# OmniBotRemote.net
KiCad netlist of a schematic drawn in Altium Designer
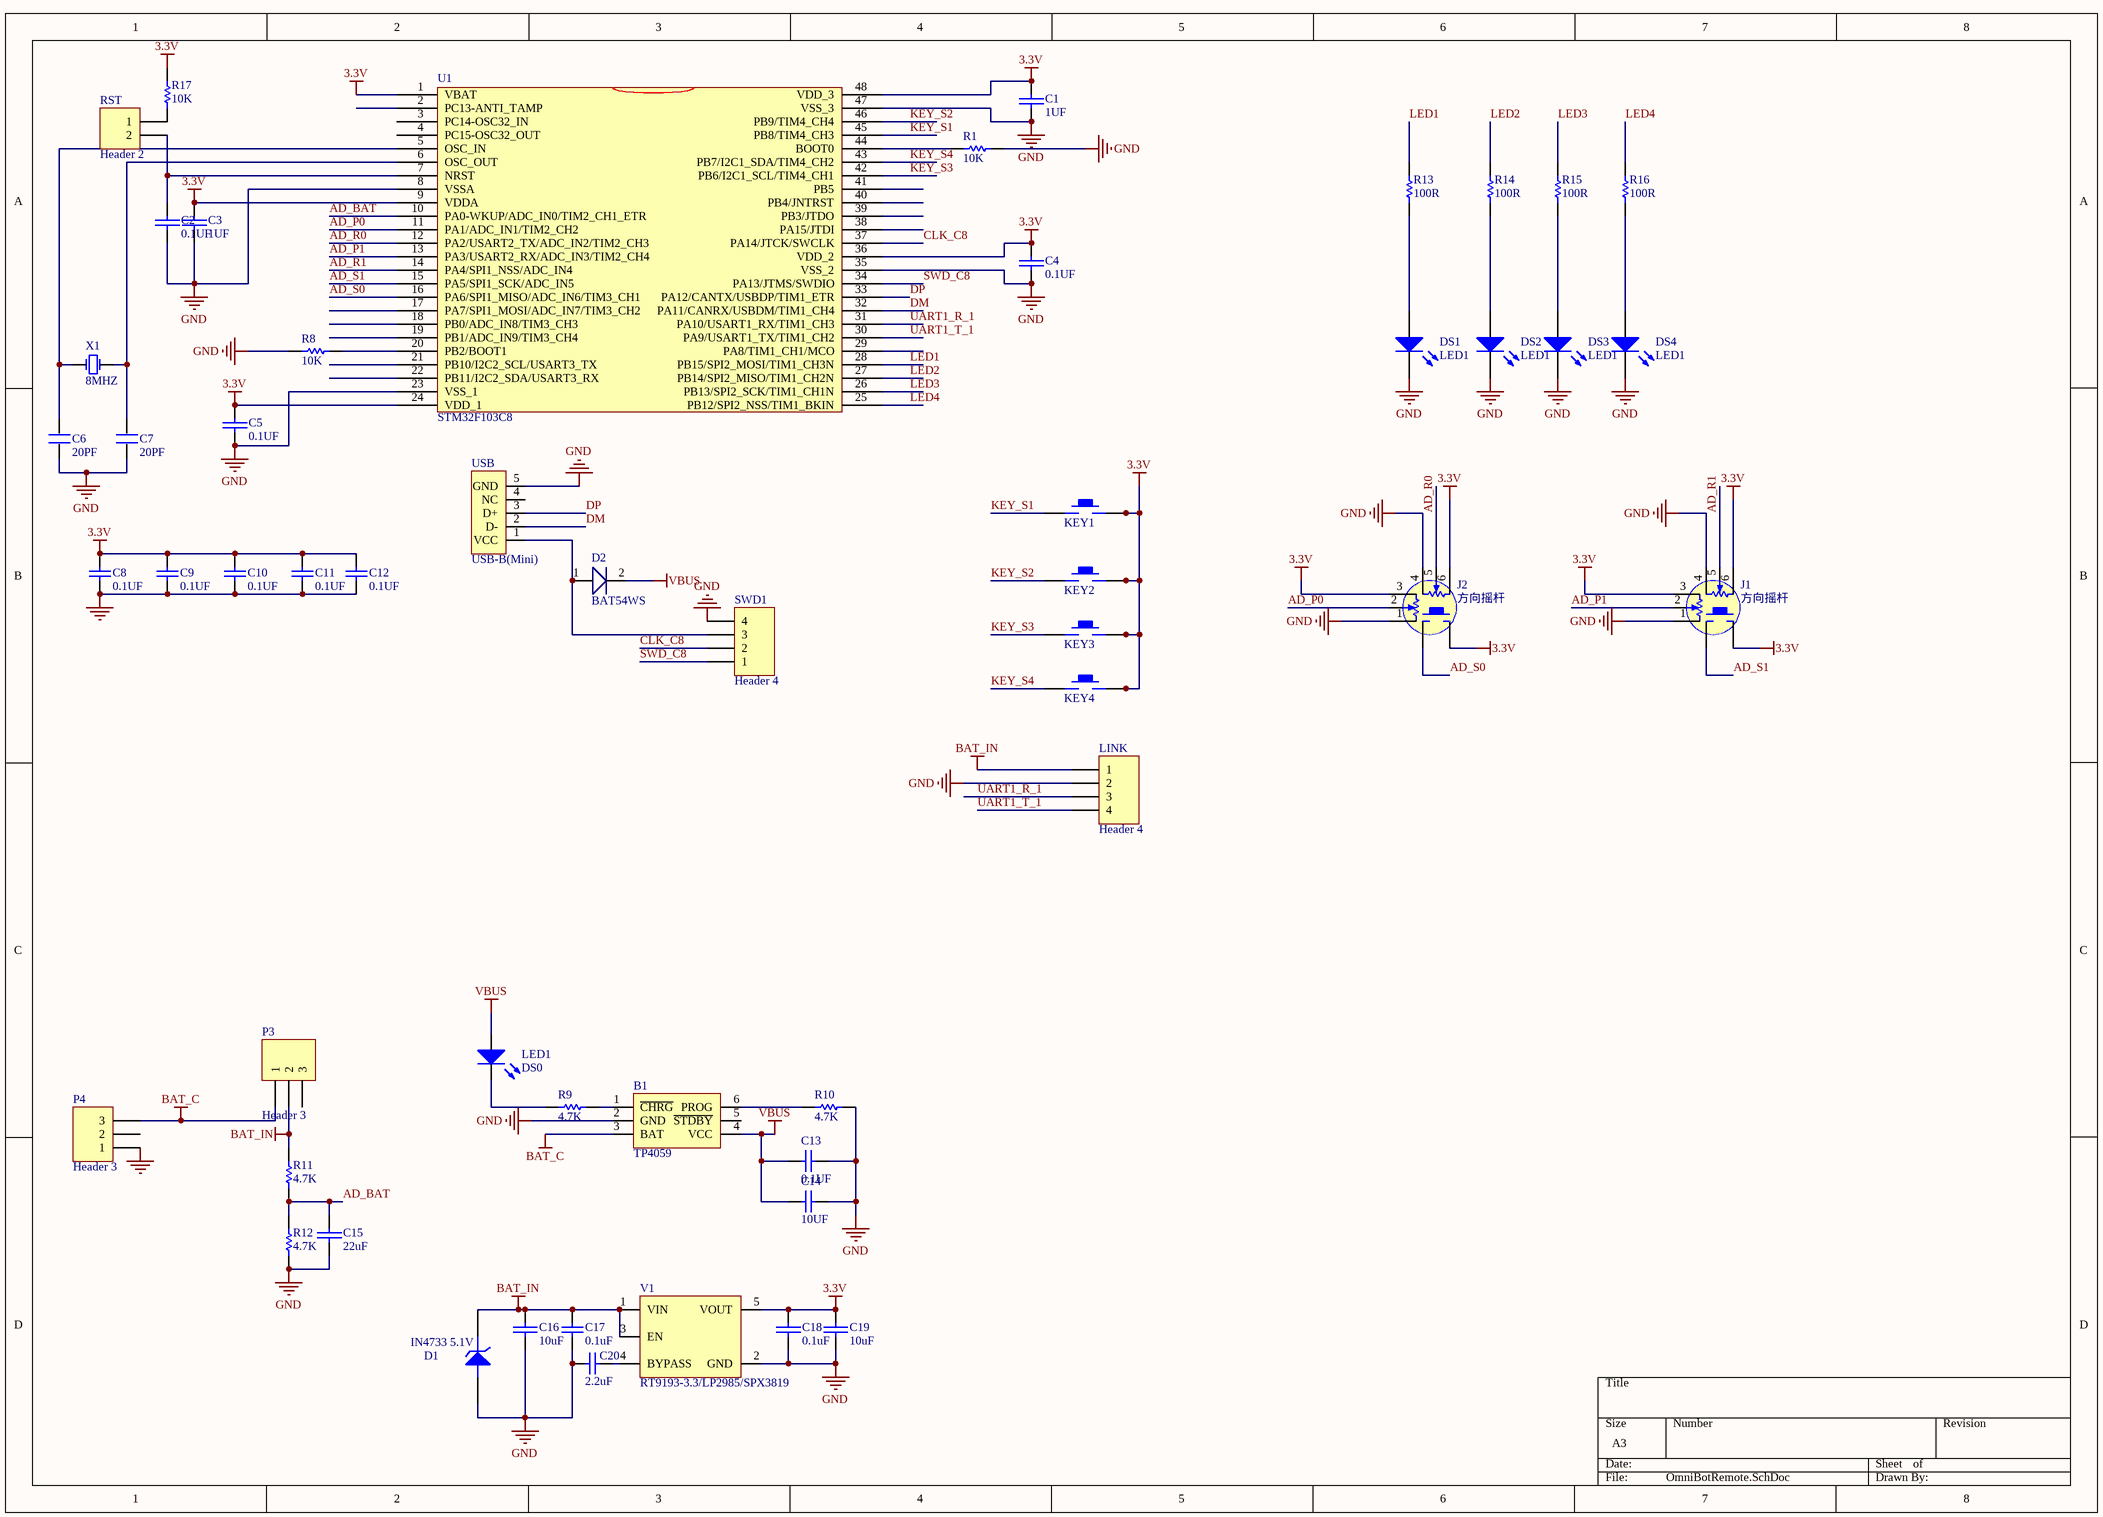
[diagram p0: OmniBotRemote.SchDoc]

(export (version "E")
  (design (tool "Eeschema 10.0.6"))
  (components
    (comp (ref "B1") (value "TP4059") (footprint "SOT23-6S") (libsource (lib "MiniFly ") (part "TP4059")))
    (comp (ref "C1")
      (value "1UF")
      (footprint "C 0402")
      (description "Capacitor")
      (libsource (lib "*") (part "CAP"))
    )
    (comp (ref "C2")
      (value "0.1UF")
      (footprint "C 0402")
      (description "Capacitor")
      (libsource (lib "*") (part "CAP"))
    )
    (comp (ref "C3")
      (value "1UF")
      (footprint "C 0402")
      (description "Capacitor")
      (libsource (lib "*") (part "CAP"))
    )
    (comp (ref "C4")
      (value "0.1UF")
      (footprint "C 0402")
      (description "Capacitor")
      (libsource (lib "*") (part "CAP"))
    )
    (comp (ref "C5")
      (value "0.1UF")
      (footprint "C 0402")
      (description "Capacitor")
      (libsource (lib "*") (part "CAP"))
    )
    (comp (ref "C6")
      (value "20PF")
      (footprint "C 0402")
      (description "0805")
      (libsource (lib "stm32f429i") (part "C2"))
    )
    (comp (ref "C7")
      (value "20PF")
      (footprint "C 0402")
      (description "0805")
      (libsource (lib "stm32f429i") (part "C2"))
    )
    (comp (ref "C8")
      (value "0.1UF")
      (footprint "C 0402")
      (description "Capacitor")
      (fields (field (name "PUBLISHER") "Altium Limited"))
      (libsource (lib "Miscellaneous Devices") (part "CAP"))
    )
    (comp (ref "C9")
      (value "0.1UF")
      (footprint "C 0402")
      (description "Capacitor")
      (fields (field (name "PUBLISHER") "Altium Limited"))
      (libsource (lib "Miscellaneous Devices") (part "CAP"))
    )
    (comp (ref "C10")
      (value "0.1UF")
      (footprint "C 0402")
      (description "Capacitor")
      (fields (field (name "PUBLISHER") "Altium Limited"))
      (libsource (lib "Miscellaneous Devices") (part "CAP"))
    )
    (comp (ref "C11")
      (value "0.1UF")
      (footprint "C 0402")
      (description "Capacitor")
      (fields (field (name "PUBLISHER") "Altium Limited"))
      (libsource (lib "Miscellaneous Devices") (part "CAP"))
    )
    (comp (ref "C12")
      (value "0.1UF")
      (footprint "C 0402")
      (description "Capacitor")
      (fields (field (name "PUBLISHER") "Altium Limited"))
      (libsource (lib "Miscellaneous Devices") (part "CAP"))
    )
    (comp (ref "C13")
      (value "0.1UF")
      (footprint "C0603")
      (description "Capacitor")
      (fields (field (name "PUBLISHER") "Altium Limited"))
      (libsource (lib "Miscellaneous Devices") (part "CAP"))
    )
    (comp (ref "C14")
      (value "10UF")
      (footprint "C0603")
      (description "Capacitor")
      (fields (field (name "PUBLISHER") "Altium Limited"))
      (libsource (lib "Miscellaneous Devices") (part "CAP"))
    )
    (comp (ref "C15")
      (value "22uF")
      (footprint "C 0402")
      (description "Capacitor")
      (libsource (lib "*") (part "CAP"))
    )
    (comp (ref "C16")
      (value "10uF")
      (footprint "C0603")
      (description "Capacitor")
      (libsource (lib "*") (part "CAP"))
    )
    (comp (ref "C17")
      (value "0.1uF")
      (footprint "C 0402")
      (description "普通电容")
      (fields (field (name "PUBLISHER") "Altium Limited"))
      (libsource (lib "HX_AD") (part "Capacitor"))
    )
    (comp (ref "C18")
      (value "0.1uF")
      (footprint "C 0402")
      (description "Capacitor")
      (libsource (lib "*") (part "CAP"))
    )
    (comp (ref "C19")
      (value "10uF")
      (footprint "C0603")
      (description "Capacitor")
      (libsource (lib "*") (part "CAP"))
    )
    (comp (ref "C20")
      (value "2.2uF")
      (footprint "C 0402")
      (description "普通电容")
      (fields (field (name "Comment") "0.1uF") (field (name "PUBLISHER") "Altium Limited"))
      (libsource (lib "HX_AD") (part "Capacitor"))
    )
    (comp (ref "D1")
      (value "IN4733 5.1V")
      (footprint "1n4148-SOD123")
      (description "Zener Diode")
      (libsource (lib "*") (part "ZENER3"))
    )
    (comp (ref "D2")
      (value "BAT54WS")
      (footprint "SOD-323")
      (description "单肖特基二极管")
      (libsource (lib "MiniFly ") (part "BAT54"))
    )
    (comp (ref "DS1")
      (value "LED1")
      (footprint "SMDLED")
      (description "Typical RED, GREEN, YELLOW, AMBER GaAs LED")
      (fields (field (name "PUBLISHER") "Altium Limited"))
      (libsource (lib "EXPLORER") (part "LED2"))
    )
    (comp (ref "DS2")
      (value "LED1")
      (footprint "SMDLED")
      (description "Typical RED, GREEN, YELLOW, AMBER GaAs LED")
      (fields (field (name "PUBLISHER") "Altium Limited"))
      (libsource (lib "EXPLORER") (part "LED2"))
    )
    (comp (ref "DS3")
      (value "LED1")
      (footprint "SMDLED")
      (description "Typical RED, GREEN, YELLOW, AMBER GaAs LED")
      (fields (field (name "PUBLISHER") "Altium Limited"))
      (libsource (lib "EXPLORER") (part "LED2"))
    )
    (comp (ref "DS4")
      (value "LED1")
      (footprint "SMDLED")
      (description "Typical RED, GREEN, YELLOW, AMBER GaAs LED")
      (fields (field (name "PUBLISHER") "Altium Limited"))
      (libsource (lib "EXPLORER") (part "LED2"))
    )
    (comp (ref "J1")
      (value "方向摇杆")
      (footprint "摇杆2")
      (description "摇杆")
      (libsource (lib "REMOTOR V1.6") (part "摇杆_1"))
    )
    (comp (ref "J2")
      (value "方向摇杆")
      (footprint "摇杆2")
      (description "摇杆")
      (libsource (lib "REMOTOR V1.6") (part "摇杆_1"))
    )
    (comp (ref "KEY1") (value "KEY_M") (footprint "KEY_M") (libsource (lib "EXPLORER") (part "KEY_M")))
    (comp (ref "KEY2") (value "KEY_M") (footprint "KEY_M") (libsource (lib "EXPLORER") (part "KEY_M")))
    (comp (ref "KEY3") (value "KEY_M") (footprint "KEY_M") (libsource (lib "EXPLORER") (part "KEY_M")))
    (comp (ref "KEY4") (value "KEY_M") (footprint "KEY_M") (libsource (lib "EXPLORER") (part "KEY_M")))
    (comp (ref "LED1")
      (value "DS0")
      (footprint "LED_0603")
      (description "Typical RED, GREEN, YELLOW, AMBER GaAs LED")
      (fields (field (name "PUBLISHER") "Altium Limited"))
      (libsource (lib "stm32f429i") (part "LED"))
    )
    (comp (ref "LINK")
      (value "Header 4")
      (footprint "HDR2X2")
      (description "Header, 4-Pin")
      (fields (field (name "PUBLISHER") "Altium Limited"))
      (libsource (lib "") (part "Header 4_1"))
    )
    (comp (ref "P3")
      (value "Header 3")
      (footprint "HDR1X3")
      (description "Header, 3-Pin")
      (fields (field (name "PUBLISHER") "Altium Limited"))
      (libsource (lib "Miscellaneous Connectors") (part "Header 3"))
    )
    (comp (ref "P4")
      (value "Header 3")
      (footprint "HDR1X3")
      (description "Header, 3-Pin")
      (fields (field (name "PUBLISHER") "Altium Limited"))
      (libsource (lib "") (part "Header 3_1"))
    )
    (comp (ref "R1")
      (value "10K")
      (footprint "R 0402")
      (description "Resistor")
      (fields (field (name "Comment") "1K") (field (name "PUBLISHER") "Altium Limited"))
      (libsource (lib "Miscellaneous Devices") (part "Res1"))
    )
    (comp (ref "R8")
      (value "10K")
      (footprint "R 0402")
      (description "Resistor")
      (fields (field (name "Comment") "1K") (field (name "PUBLISHER") "Altium Limited"))
      (libsource (lib "Miscellaneous Devices") (part "Res1"))
    )
    (comp (ref "R9")
      (value "4.7K")
      (footprint "R0603")
      (description "Resistor")
      (fields (field (name "Comment") "1K") (field (name "PUBLISHER") "Altium Limited"))
      (libsource (lib "Miscellaneous Devices") (part "Res1"))
    )
    (comp (ref "R10")
      (value "4.7K")
      (footprint "R0603")
      (description "Resistor")
      (fields (field (name "Comment") "1K") (field (name "PUBLISHER") "Altium Limited"))
      (libsource (lib "Miscellaneous Devices") (part "Res1"))
    )
    (comp (ref "R11")
      (value "4.7K")
      (footprint "R 0402")
      (description "0603")
      (libsource (lib "stm32f429i") (part "Res2"))
    )
    (comp (ref "R12")
      (value "4.7K")
      (footprint "R 0402")
      (description "0603")
      (libsource (lib "stm32f429i") (part "Res2"))
    )
    (comp (ref "R13")
      (value "100R")
      (footprint "R0603")
      (description "0603")
      (libsource (lib "stm32f429i") (part "Res2"))
    )
    (comp (ref "R14")
      (value "100R")
      (footprint "R0603")
      (description "0603")
      (libsource (lib "stm32f429i") (part "Res2"))
    )
    (comp (ref "R15")
      (value "100R")
      (footprint "R0603")
      (description "0603")
      (libsource (lib "stm32f429i") (part "Res2"))
    )
    (comp (ref "R16")
      (value "100R")
      (footprint "R0603")
      (description "0603")
      (libsource (lib "stm32f429i") (part "Res2"))
    )
    (comp (ref "R17")
      (value "10K")
      (footprint "R0603")
      (description "0603")
      (libsource (lib "stm32f429i") (part "Res2"))
    )
    (comp (ref "RST")
      (value "Header 2")
      (footprint "KEY_SAD")
      (description "Header, 2-Pin")
      (fields (field (name "PUBLISHER") "Altium Limited"))
      (libsource (lib "Miscellaneous Connectors") (part "Header 2"))
    )
    (comp (ref "SWD1")
      (value "Header 4")
      (footprint "SH1.0-4P - up")
      (description "Header, 4-Pin")
      (fields (field (name "PUBLISHER") "Altium Limited"))
      (libsource (lib "Explorer STM32F407封装库") (part "Header 4"))
    )
    (comp (ref "U1")
      (value "STM32F103C8")
      (footprint "LQFP48S")
      (libsource (lib "STM32") (part "STM32F103C6"))
    )
    (comp (ref "USB")
      (value "USB-B(Mini)")
      (footprint "USB/SM0.8-6H5_M")
      (libsource (lib "EXPLORER") (part "USB5"))
    )
    (comp (ref "V1")
      (value "RT9193-3.3/LP2985/SPX3819")
      (footprint "SOT23-5")
      (description "降压IC")
      (libsource (lib "HX_AD") (part "RT9193-3.3/LP2985/SPX3819"))
    )
    (comp (ref "X1")
      (value "8MHZ")
      (footprint "PXCL")
      (description "Crystal Oscillator")
      (fields (field (name "PUBLISHER") "Altium Limited"))
      (libsource (lib "stm32f429i") (part "XTAL"))
    )
  )
  (nets
    (net (code "1") (name "/AD_BAT") (class "Default")
      (node (ref "C15") (pin "1") (pinfunction "1_1") (pintype "passive"))
      (node (ref "R11") (pin "2") (pinfunction "2_2") (pintype "passive"))
      (node (ref "R12") (pin "2") (pinfunction "2_2") (pintype "passive"))
      (node (ref "U1") (pin "10") (pinfunction "PA0-WKUP/ADC_IN0/TIM2_CH1_ETR_10") (pintype "passive"))
    )
    (net (code "2") (name "/AD_P0") (class "Default")
      (node (ref "J2") (pin "2") (pinfunction "2_2") (pintype "passive"))
      (node (ref "U1") (pin "11") (pinfunction "PA1/ADC_IN1/TIM2_CH2_11") (pintype "passive"))
    )
    (net (code "3") (name "/AD_P1") (class "Default")
      (node (ref "J1") (pin "2") (pinfunction "2_2") (pintype "passive"))
      (node (ref "U1") (pin "13") (pinfunction "PA3/USART2_RX/ADC_IN3/TIM2_CH4_13") (pintype "passive"))
    )
    (net (code "4") (name "/AD_R0") (class "Default")
      (node (ref "J2") (pin "5") (pinfunction "5_5") (pintype "passive"))
      (node (ref "U1") (pin "12") (pinfunction "PA2/USART2_TX/ADC_IN2/TIM2_CH3_12") (pintype "passive"))
    )
    (net (code "5") (name "/AD_R1") (class "Default")
      (node (ref "J1") (pin "5") (pinfunction "5_5") (pintype "passive"))
      (node (ref "U1") (pin "14") (pinfunction "PA4/SPI1_NSS/ADC_IN4_14") (pintype "passive"))
    )
    (net (code "6") (name "/AD_S0") (class "Default")
      (node (ref "J2") (pin "J2") (pinfunction "J2_J2") (pintype "passive"))
      (node (ref "U1") (pin "16") (pinfunction "PA6/SPI1_MISO/ADC_IN6/TIM3_CH1_16") (pintype "passive"))
    )
    (net (code "7") (name "/AD_S1") (class "Default")
      (node (ref "J1") (pin "J2") (pinfunction "J2_J2") (pintype "passive"))
      (node (ref "U1") (pin "15") (pinfunction "PA5/SPI1_SCK/ADC_IN5_15") (pintype "passive"))
    )
    (net (code "8") (name "/CLK_C8") (class "Default")
      (node (ref "SWD1") (pin "2") (pinfunction "2_2") (pintype "passive"))
      (node (ref "U1") (pin "37") (pinfunction "PA14/JTCK/SWCLK_37") (pintype "passive"))
    )
    (net (code "9") (name "/DM") (class "Default")
      (node (ref "U1") (pin "32") (pinfunction "PA11/CANRX/USBDM/TIM1_CH4_32") (pintype "passive"))
      (node (ref "USB") (pin "2") (pinfunction "D-_2") (pintype "passive"))
    )
    (net (code "10") (name "/DP") (class "Default")
      (node (ref "U1") (pin "33") (pinfunction "PA12/CANTX/USBDP/TIM1_ETR_33") (pintype "passive"))
      (node (ref "USB") (pin "3") (pinfunction "D+_3") (pintype "passive"))
    )
    (net (code "11") (name "/KEY_S1") (class "Default")
      (node (ref "KEY1") (pin "1") (pinfunction "1_1") (pintype "passive"))
      (node (ref "U1") (pin "45") (pinfunction "PB8/TIM4_CH3_45") (pintype "passive"))
    )
    (net (code "12") (name "/KEY_S2") (class "Default")
      (node (ref "KEY2") (pin "1") (pinfunction "1_1") (pintype "passive"))
      (node (ref "U1") (pin "46") (pinfunction "PB9/TIM4_CH4_46") (pintype "passive"))
    )
    (net (code "13") (name "/KEY_S3") (class "Default")
      (node (ref "KEY3") (pin "1") (pinfunction "1_1") (pintype "passive"))
      (node (ref "U1") (pin "42") (pinfunction "PB6/I2C1_SCL/TIM4_CH1_42") (pintype "passive"))
    )
    (net (code "14") (name "/KEY_S4") (class "Default")
      (node (ref "KEY4") (pin "1") (pinfunction "1_1") (pintype "passive"))
      (node (ref "U1") (pin "43") (pinfunction "PB7/I2C1_SDA/TIM4_CH2_43") (pintype "passive"))
    )
    (net (code "15") (name "/LED1") (class "Default")
      (node (ref "R13") (pin "1") (pinfunction "1_1") (pintype "passive"))
      (node (ref "U1") (pin "28") (pinfunction "PB15/SPI2_MOSI/TIM1_CH3N_28") (pintype "passive"))
    )
    (net (code "16") (name "/LED2") (class "Default")
      (node (ref "R14") (pin "1") (pinfunction "1_1") (pintype "passive"))
      (node (ref "U1") (pin "27") (pinfunction "PB14/SPI2_MISO/TIM1_CH2N_27") (pintype "passive"))
    )
    (net (code "17") (name "/LED3") (class "Default")
      (node (ref "R15") (pin "1") (pinfunction "1_1") (pintype "passive"))
      (node (ref "U1") (pin "26") (pinfunction "PB13/SPI2_SCK/TIM1_CH1N_26") (pintype "passive"))
    )
    (net (code "18") (name "/LED4") (class "Default")
      (node (ref "R16") (pin "1") (pinfunction "1_1") (pintype "passive"))
      (node (ref "U1") (pin "25") (pinfunction "PB12/SPI2_NSS/TIM1_BKIN_25") (pintype "passive"))
    )
    (net (code "19") (name "/SWD_C8") (class "Default")
      (node (ref "SWD1") (pin "1") (pinfunction "1_1") (pintype "passive"))
      (node (ref "U1") (pin "34") (pinfunction "PA13/JTMS/SWDIO_34") (pintype "passive"))
    )
    (net (code "20") (name "/UART1_R_1") (class "Default")
      (node (ref "LINK") (pin "3") (pinfunction "3_3") (pintype "passive"))
      (node (ref "U1") (pin "31") (pinfunction "PA10/USART1_RX/TIM1_CH3_31") (pintype "passive"))
    )
    (net (code "21") (name "/UART1_T_1") (class "Default")
      (node (ref "LINK") (pin "4") (pinfunction "4_4") (pintype "passive"))
      (node (ref "U1") (pin "30") (pinfunction "PA9/USART1_TX/TIM1_CH2_30") (pintype "passive"))
    )
    (net (code "22") (name "3.3V") (class "Default")
      (node (ref "C1") (pin "2") (pinfunction "2_2") (pintype "passive"))
      (node (ref "C10") (pin "1") (pinfunction "1_1") (pintype "passive"))
      (node (ref "C11") (pin "1") (pinfunction "1_1") (pintype "passive"))
      (node (ref "C12") (pin "1") (pinfunction "1_1") (pintype "passive"))
      (node (ref "C18") (pin "1") (pinfunction "1_1") (pintype "passive"))
      (node (ref "C19") (pin "1") (pinfunction "1_1") (pintype "passive"))
      (node (ref "C3") (pin "2") (pinfunction "2_2") (pintype "passive"))
      (node (ref "C4") (pin "2") (pinfunction "2_2") (pintype "passive"))
      (node (ref "C5") (pin "2") (pinfunction "2_2") (pintype "passive"))
      (node (ref "C8") (pin "1") (pinfunction "1_1") (pintype "passive"))
      (node (ref "C9") (pin "1") (pinfunction "1_1") (pintype "passive"))
      (node (ref "J1") (pin "3") (pinfunction "3_3") (pintype "passive"))
      (node (ref "J1") (pin "6") (pinfunction "6_6") (pintype "passive"))
      (node (ref "J1") (pin "J1") (pinfunction "J1_J1") (pintype "passive"))
      (node (ref "J2") (pin "3") (pinfunction "3_3") (pintype "passive"))
      (node (ref "J2") (pin "6") (pinfunction "6_6") (pintype "passive"))
      (node (ref "J2") (pin "J1") (pinfunction "J1_J1") (pintype "passive"))
      (node (ref "KEY1") (pin "2") (pinfunction "2_2") (pintype "passive"))
      (node (ref "KEY2") (pin "2") (pinfunction "2_2") (pintype "passive"))
      (node (ref "KEY3") (pin "2") (pinfunction "2_2") (pintype "passive"))
      (node (ref "KEY4") (pin "2") (pinfunction "2_2") (pintype "passive"))
      (node (ref "R17") (pin "2") (pinfunction "2_2") (pintype "passive"))
      (node (ref "U1") (pin "1") (pinfunction "VBAT_1") (pintype "passive"))
      (node (ref "U1") (pin "24") (pinfunction "VDD_1_24") (pintype "passive"))
      (node (ref "U1") (pin "36") (pinfunction "VDD_2_36") (pintype "passive"))
      (node (ref "U1") (pin "48") (pinfunction "VDD_3_48") (pintype "passive"))
      (node (ref "U1") (pin "9") (pinfunction "VDDA_9") (pintype "passive"))
      (node (ref "V1") (pin "5") (pinfunction "VOUT_5") (pintype "passive"))
    )
    (net (code "23") (name "BAT_C") (class "Default")
      (node (ref "B1") (pin "3") (pinfunction "BAT_3") (pintype "passive"))
      (node (ref "P3") (pin "1") (pinfunction "1_1") (pintype "passive"))
      (node (ref "P4") (pin "3") (pinfunction "3_3") (pintype "passive"))
    )
    (net (code "24") (name "BAT_IN") (class "Default")
      (node (ref "C16") (pin "1") (pinfunction "1_1") (pintype "passive"))
      (node (ref "C17") (pin "2") (pinfunction "2_2") (pintype "passive"))
      (node (ref "D1") (pin "2") (pinfunction "K_2") (pintype "passive"))
      (node (ref "LINK") (pin "1") (pinfunction "1_1") (pintype "passive"))
      (node (ref "P3") (pin "2") (pinfunction "2_2") (pintype "passive"))
      (node (ref "R11") (pin "1") (pinfunction "1_1") (pintype "passive"))
      (node (ref "V1") (pin "1") (pinfunction "VIN_1") (pintype "passive"))
      (node (ref "V1") (pin "3") (pinfunction "EN_3") (pintype "passive"))
    )
    (net (code "25") (name "GND") (class "Default")
      (node (ref "B1") (pin "2") (pinfunction "GND_2") (pintype "passive"))
      (node (ref "C1") (pin "1") (pinfunction "1_1") (pintype "passive"))
      (node (ref "C10") (pin "2") (pinfunction "2_2") (pintype "passive"))
      (node (ref "C11") (pin "2") (pinfunction "2_2") (pintype "passive"))
      (node (ref "C12") (pin "2") (pinfunction "2_2") (pintype "passive"))
      (node (ref "C13") (pin "1") (pinfunction "1_1") (pintype "passive"))
      (node (ref "C14") (pin "1") (pinfunction "1_1") (pintype "passive"))
      (node (ref "C15") (pin "2") (pinfunction "2_2") (pintype "passive"))
      (node (ref "C16") (pin "2") (pinfunction "2_2") (pintype "passive"))
      (node (ref "C17") (pin "1") (pinfunction "1_1") (pintype "passive"))
      (node (ref "C18") (pin "2") (pinfunction "2_2") (pintype "passive"))
      (node (ref "C19") (pin "2") (pinfunction "2_2") (pintype "passive"))
      (node (ref "C2") (pin "1") (pinfunction "1_1") (pintype "passive"))
      (node (ref "C20") (pin "2") (pinfunction "2_2") (pintype "passive"))
      (node (ref "C3") (pin "1") (pinfunction "1_1") (pintype "passive"))
      (node (ref "C4") (pin "1") (pinfunction "1_1") (pintype "passive"))
      (node (ref "C5") (pin "1") (pinfunction "1_1") (pintype "passive"))
      (node (ref "C6") (pin "1") (pintype "passive"))
      (node (ref "C7") (pin "1") (pintype "passive"))
      (node (ref "C8") (pin "2") (pinfunction "2_2") (pintype "passive"))
      (node (ref "C9") (pin "2") (pinfunction "2_2") (pintype "passive"))
      (node (ref "D1") (pin "1") (pinfunction "A_1") (pintype "passive"))
      (node (ref "DS1") (pin "2") (pinfunction "K_2") (pintype "passive"))
      (node (ref "DS2") (pin "2") (pinfunction "K_2") (pintype "passive"))
      (node (ref "DS3") (pin "2") (pinfunction "K_2") (pintype "passive"))
      (node (ref "DS4") (pin "2") (pinfunction "K_2") (pintype "passive"))
      (node (ref "J1") (pin "1") (pinfunction "1_1") (pintype "passive"))
      (node (ref "J1") (pin "4") (pinfunction "4_4") (pintype "passive"))
      (node (ref "J2") (pin "1") (pinfunction "1_1") (pintype "passive"))
      (node (ref "J2") (pin "4") (pinfunction "4_4") (pintype "passive"))
      (node (ref "LINK") (pin "2") (pinfunction "2_2") (pintype "passive"))
      (node (ref "P4") (pin "1") (pinfunction "1_1") (pintype "passive"))
      (node (ref "R1") (pin "2") (pinfunction "2_2") (pintype "passive"))
      (node (ref "R10") (pin "1") (pinfunction "1_1") (pintype "passive"))
      (node (ref "R12") (pin "1") (pinfunction "1_1") (pintype "passive"))
      (node (ref "R8") (pin "1") (pinfunction "1_1") (pintype "passive"))
      (node (ref "SWD1") (pin "4") (pinfunction "4_4") (pintype "passive"))
      (node (ref "U1") (pin "23") (pinfunction "VSS_1_23") (pintype "passive"))
      (node (ref "U1") (pin "35") (pinfunction "VSS_2_35") (pintype "passive"))
      (node (ref "U1") (pin "47") (pinfunction "VSS_3_47") (pintype "passive"))
      (node (ref "U1") (pin "8") (pinfunction "VSSA_8") (pintype "passive"))
      (node (ref "USB") (pin "5") (pinfunction "GND_5") (pintype "passive"))
      (node (ref "V1") (pin "2") (pinfunction "GND_2") (pintype "passive"))
    )
    (net (code "26") (name "Net-(B1-PROG)") (class "Default")
      (node (ref "B1") (pin "6") (pinfunction "PROG_6") (pintype "passive"))
      (node (ref "R10") (pin "2") (pinfunction "2_2") (pintype "passive"))
    )
    (net (code "27") (name "Net-(B1-~{CHRG})") (class "Default")
      (node (ref "B1") (pin "1") (pinfunction "~{CHRG}_1") (pintype "passive"))
      (node (ref "R9") (pin "1") (pinfunction "1_1") (pintype "passive"))
    )
    (net (code "28") (name "Net-(DS1-A)") (class "Default")
      (node (ref "DS1") (pin "1") (pinfunction "A_1") (pintype "passive"))
      (node (ref "R13") (pin "2") (pinfunction "2_2") (pintype "passive"))
    )
    (net (code "29") (name "Net-(DS2-A)") (class "Default")
      (node (ref "DS2") (pin "1") (pinfunction "A_1") (pintype "passive"))
      (node (ref "R14") (pin "2") (pinfunction "2_2") (pintype "passive"))
    )
    (net (code "30") (name "Net-(DS3-A)") (class "Default")
      (node (ref "DS3") (pin "1") (pinfunction "A_1") (pintype "passive"))
      (node (ref "R15") (pin "2") (pinfunction "2_2") (pintype "passive"))
    )
    (net (code "31") (name "Net-(DS4-A)") (class "Default")
      (node (ref "DS4") (pin "1") (pinfunction "A_1") (pintype "passive"))
      (node (ref "R16") (pin "2") (pinfunction "2_2") (pintype "passive"))
    )
    (net (code "32") (name "Net-(LED1-K)") (class "Default")
      (node (ref "LED1") (pin "2") (pinfunction "K_2") (pintype "passive"))
      (node (ref "R9") (pin "2") (pinfunction "2_2") (pintype "passive"))
    )
    (net (code "33") (name "Net-(R17-Pad1)") (class "Default")
      (node (ref "R17") (pin "1") (pinfunction "1_1") (pintype "passive"))
      (node (ref "RST") (pin "1") (pinfunction "1_1") (pintype "passive"))
    )
    (net (code "34") (name "Net-(U1-BOOT0)") (class "Default")
      (node (ref "R1") (pin "1") (pinfunction "1_1") (pintype "passive"))
      (node (ref "U1") (pin "44") (pinfunction "BOOT0_44") (pintype "passive"))
    )
    (net (code "35") (name "Net-(U1-NRST)") (class "Default")
      (node (ref "C2") (pin "2") (pinfunction "2_2") (pintype "passive"))
      (node (ref "RST") (pin "2") (pinfunction "2_2") (pintype "passive"))
      (node (ref "U1") (pin "7") (pinfunction "NRST_7") (pintype "passive"))
    )
    (net (code "36") (name "Net-(U1-OSC_IN)") (class "Default")
      (node (ref "C6") (pin "2") (pintype "passive"))
      (node (ref "U1") (pin "5") (pinfunction "OSC_IN_5") (pintype "passive"))
      (node (ref "X1") (pin "1") (pinfunction "OSC1_1") (pintype "passive"))
    )
    (net (code "37") (name "Net-(U1-OSC_OUT)") (class "Default")
      (node (ref "C7") (pin "2") (pintype "passive"))
      (node (ref "U1") (pin "6") (pinfunction "OSC_OUT_6") (pintype "passive"))
      (node (ref "X1") (pin "2") (pinfunction "OSC2_2") (pintype "passive"))
    )
    (net (code "38") (name "Net-(U1-PB2{slash}BOOT1)") (class "Default")
      (node (ref "R8") (pin "2") (pinfunction "2_2") (pintype "passive"))
      (node (ref "U1") (pin "20") (pinfunction "PB2/BOOT1_20") (pintype "passive"))
    )
    (net (code "39") (name "Net-(USB-VCC)") (class "Default")
      (node (ref "D2") (pin "1") (pinfunction "1_1") (pintype "passive"))
      (node (ref "SWD1") (pin "3") (pinfunction "3_3") (pintype "passive"))
      (node (ref "USB") (pin "1") (pinfunction "VCC_1") (pintype "passive"))
    )
    (net (code "40") (name "Net-(V1-BYPASS)") (class "Default")
      (node (ref "C20") (pin "1") (pinfunction "1_1") (pintype "passive"))
      (node (ref "V1") (pin "4") (pinfunction "BYPASS_4") (pintype "passive"))
    )
    (net (code "41") (name "VBUS") (class "Default")
      (node (ref "B1") (pin "4") (pinfunction "VCC_4") (pintype "passive"))
      (node (ref "C13") (pin "2") (pinfunction "2_2") (pintype "passive"))
      (node (ref "C14") (pin "2") (pinfunction "2_2") (pintype "passive"))
      (node (ref "D2") (pin "2") (pinfunction "2_2") (pintype "passive"))
      (node (ref "LED1") (pin "1") (pinfunction "A_1") (pintype "passive"))
    )
    (net (code "42") (name "unconnected-(B1-~{STDBY}-Pad5)") (class "Default")
      (node (ref "B1") (pin "5") (pinfunction "~{STDBY}_5") (pintype "passive"))
    )
    (net (code "43") (name "unconnected-(P3-Pad3)") (class "Default")
      (node (ref "P3") (pin "3") (pinfunction "3_3") (pintype "passive"))
    )
    (net (code "44") (name "unconnected-(P4-Pad2)") (class "Default")
      (node (ref "P4") (pin "2") (pinfunction "2_2") (pintype "passive"))
    )
    (net (code "45") (name "unconnected-(U1-PA7{slash}SPI1_MOSI{slash}ADC_IN7{slash}TIM3_CH2-Pad17)") (class "Default")
      (node (ref "U1") (pin "17") (pinfunction "PA7/SPI1_MOSI/ADC_IN7/TIM3_CH2_17") (pintype "passive"))
    )
    (net (code "46") (name "unconnected-(U1-PA8{slash}TIM1_CH1{slash}MCO-Pad29)") (class "Default")
      (node (ref "U1") (pin "29") (pinfunction "PA8/TIM1_CH1/MCO_29") (pintype "passive"))
    )
    (net (code "47") (name "unconnected-(U1-PA15{slash}JTDI-Pad38)") (class "Default")
      (node (ref "U1") (pin "38") (pinfunction "PA15/JTDI_38") (pintype "passive"))
    )
    (net (code "48") (name "unconnected-(U1-PB0{slash}ADC_IN8{slash}TIM3_CH3-Pad18)") (class "Default")
      (node (ref "U1") (pin "18") (pinfunction "PB0/ADC_IN8/TIM3_CH3_18") (pintype "passive"))
    )
    (net (code "49") (name "unconnected-(U1-PB1{slash}ADC_IN9{slash}TIM3_CH4-Pad19)") (class "Default")
      (node (ref "U1") (pin "19") (pinfunction "PB1/ADC_IN9/TIM3_CH4_19") (pintype "passive"))
    )
    (net (code "50") (name "unconnected-(U1-PB3{slash}JTDO-Pad39)") (class "Default")
      (node (ref "U1") (pin "39") (pinfunction "PB3/JTDO_39") (pintype "passive"))
    )
    (net (code "51") (name "unconnected-(U1-PB4{slash}JNTRST-Pad40)") (class "Default")
      (node (ref "U1") (pin "40") (pinfunction "PB4/JNTRST_40") (pintype "passive"))
    )
    (net (code "52") (name "unconnected-(U1-PB5-Pad41)") (class "Default")
      (node (ref "U1") (pin "41") (pinfunction "PB5_41") (pintype "passive"))
    )
    (net (code "53") (name "unconnected-(U1-PB10{slash}I2C2_SCL{slash}USART3_TX-Pad21)") (class "Default")
      (node (ref "U1") (pin "21") (pinfunction "PB10/I2C2_SCL/USART3_TX_21") (pintype "passive"))
    )
    (net (code "54") (name "unconnected-(U1-PB11{slash}I2C2_SDA{slash}USART3_RX-Pad22)") (class "Default")
      (node (ref "U1") (pin "22") (pinfunction "PB11/I2C2_SDA/USART3_RX_22") (pintype "passive"))
    )
    (net (code "55") (name "unconnected-(U1-PC13-ANTI_TAMP-Pad2)") (class "Default")
      (node (ref "U1") (pin "2") (pinfunction "PC13-ANTI_TAMP_2") (pintype "passive"))
    )
    (net (code "56") (name "unconnected-(U1-PC14-OSC32_IN-Pad3)") (class "Default")
      (node (ref "U1") (pin "3") (pinfunction "PC14-OSC32_IN_3") (pintype "passive"))
    )
    (net (code "57") (name "unconnected-(U1-PC15-OSC32_OUT-Pad4)") (class "Default")
      (node (ref "U1") (pin "4") (pinfunction "PC15-OSC32_OUT_4") (pintype "passive"))
    )
    (net (code "58") (name "unconnected-(USB-NC-Pad4)") (class "Default")
      (node (ref "USB") (pin "4") (pinfunction "NC_4") (pintype "passive"))
    )
  )
)
